# Arm.net
KiCad netlist of a schematic drawn in EAGLE
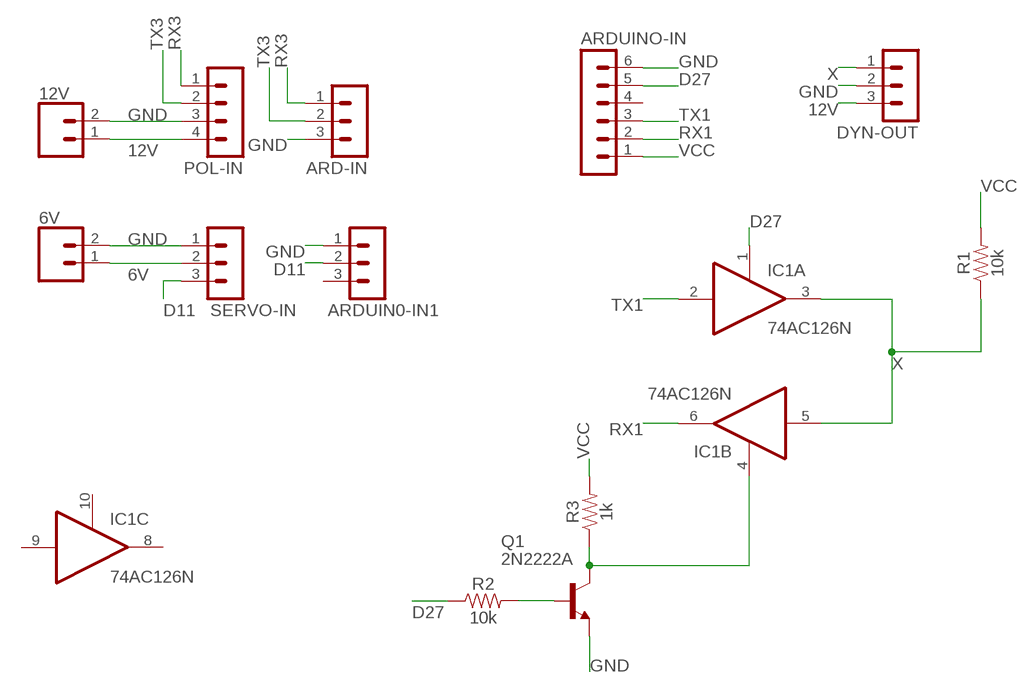
[diagram p0: schematic, sheet 1]

(export (version "E")
  (design (tool "Eeschema 10.0.6"))
  (components
    (comp (ref "6V")
      (value "CONN_021X02_NO_SILK")
      (footprint "eagle-import:1X02_NO_SILK")
      (libsource (lib "eagle-import") (part "CONN_021X02_NO_SILK"))
    )
    (comp (ref "12V")
      (value "CONN_021X02_NO_SILK")
      (footprint "eagle-import:1X02_NO_SILK")
      (libsource (lib "eagle-import") (part "CONN_021X02_NO_SILK"))
    )
    (comp (ref "ARD-IN")
      (value "MA03-1")
      (footprint "eagle-import:MA03-1")
      (libsource (lib "eagle-import") (part "MA03-1"))
    )
    (comp (ref "ARDUIN0-IN1")
      (value "MA03-1")
      (footprint "eagle-import:MA03-1")
      (libsource (lib "eagle-import") (part "MA03-1"))
    )
    (comp (ref "ARDUINO-IN")
      (value "MA06-1")
      (footprint "eagle-import:MA06-1")
      (libsource (lib "eagle-import") (part "MA06-1"))
    )
    (comp (ref "DYN-OUT")
      (value "MA03-1")
      (footprint "eagle-import:MA03-1")
      (libsource (lib "eagle-import") (part "MA03-1"))
    )
    (comp (ref "IC1")
      (value "74AC126N")
      (footprint "eagle-import:DIL14")
      (libsource (lib "eagle-import") (part "74126NAC"))
    )
    (comp (ref "POL-IN")
      (value "MA04-1")
      (footprint "eagle-import:MA04-1")
      (libsource (lib "eagle-import") (part "MA04-1"))
    )
    (comp (ref "Q1")
      (value "2N2222A")
      (footprint "eagle-import:TO18")
      (libsource (lib "eagle-import") (part "2N2222A"))
    )
    (comp (ref "R1")
      (value "10k")
      (footprint "eagle-import:AXIAL-0.3")
      (libsource (lib "eagle-import") (part "1KOHM-HORIZ-1/4W-1%"))
    )
    (comp (ref "R2")
      (value "10k")
      (footprint "eagle-import:AXIAL-0.3")
      (libsource (lib "eagle-import") (part "1KOHM-HORIZ-1/4W-1%"))
    )
    (comp (ref "R3")
      (value "1k")
      (footprint "eagle-import:AXIAL-0.3")
      (libsource (lib "eagle-import") (part "1KOHM-HORIZ-1/4W-1%"))
    )
    (comp (ref "SERVO-IN")
      (value "MA03-1")
      (footprint "eagle-import:MA03-1")
      (libsource (lib "eagle-import") (part "MA03-1"))
    )
  )
  (nets
    (net (code "1") (name "/6V") (class "Default")
      (node (ref "6V") (pin "1") (pinfunction "1_1") (pintype "passive"))
      (node (ref "SERVO-IN") (pin "2") (pinfunction "2_2") (pintype "passive"))
    )
    (net (code "2") (name "/12V") (class "Default")
      (node (ref "12V") (pin "1") (pinfunction "1_1") (pintype "passive"))
      (node (ref "DYN-OUT") (pin "3") (pinfunction "3_3") (pintype "passive"))
      (node (ref "POL-IN") (pin "4") (pinfunction "4_4") (pintype "passive"))
    )
    (net (code "3") (name "/D11") (class "Default")
      (node (ref "ARDUIN0-IN1") (pin "2") (pinfunction "2_2") (pintype "passive"))
      (node (ref "SERVO-IN") (pin "3") (pinfunction "3_3") (pintype "passive"))
    )
    (net (code "4") (name "/D27") (class "Default")
      (node (ref "ARDUINO-IN") (pin "5") (pinfunction "5_5") (pintype "passive"))
      (node (ref "IC1") (pin "1") (pinfunction "OE_1") (pintype "input"))
      (node (ref "R2") (pin "P$1") (pinfunction "1_P$1") (pintype "passive"))
    )
    (net (code "5") (name "/GND") (class "Default")
      (node (ref "12V") (pin "2") (pinfunction "2_2") (pintype "passive"))
      (node (ref "6V") (pin "2") (pinfunction "2_2") (pintype "passive"))
      (node (ref "ARD-IN") (pin "3") (pinfunction "3_3") (pintype "passive"))
      (node (ref "ARDUIN0-IN1") (pin "1") (pinfunction "1_1") (pintype "passive"))
      (node (ref "ARDUINO-IN") (pin "6") (pinfunction "6_6") (pintype "passive"))
      (node (ref "DYN-OUT") (pin "2") (pinfunction "2_2") (pintype "passive"))
      (node (ref "POL-IN") (pin "3") (pinfunction "3_3") (pintype "passive"))
      (node (ref "Q1") (pin "1") (pinfunction "E_1") (pintype "passive"))
      (node (ref "SERVO-IN") (pin "1") (pinfunction "1_1") (pintype "passive"))
    )
    (net (code "6") (name "/RX1") (class "Default")
      (node (ref "ARDUINO-IN") (pin "2") (pinfunction "2_2") (pintype "passive"))
      (node (ref "IC1") (pin "6") (pinfunction "O_6") (pintype "output"))
    )
    (net (code "7") (name "/RX3") (class "Default")
      (node (ref "ARD-IN") (pin "1") (pinfunction "1_1") (pintype "passive"))
      (node (ref "POL-IN") (pin "1") (pinfunction "1_1") (pintype "passive"))
    )
    (net (code "8") (name "/TX1") (class "Default")
      (node (ref "ARDUINO-IN") (pin "3") (pinfunction "3_3") (pintype "passive"))
      (node (ref "IC1") (pin "2") (pinfunction "I_2") (pintype "input"))
    )
    (net (code "9") (name "/TX3") (class "Default")
      (node (ref "ARD-IN") (pin "2") (pinfunction "2_2") (pintype "passive"))
      (node (ref "POL-IN") (pin "2") (pinfunction "2_2") (pintype "passive"))
    )
    (net (code "10") (name "/VCC") (class "Default")
      (node (ref "ARDUINO-IN") (pin "1") (pinfunction "1_1") (pintype "passive"))
      (node (ref "R1") (pin "P$2") (pinfunction "2_P$2") (pintype "passive"))
      (node (ref "R3") (pin "P$2") (pinfunction "2_P$2") (pintype "passive"))
    )
    (net (code "11") (name "/X") (class "Default")
      (node (ref "DYN-OUT") (pin "1") (pinfunction "1_1") (pintype "passive"))
      (node (ref "IC1") (pin "3") (pinfunction "O_3") (pintype "output"))
      (node (ref "IC1") (pin "5") (pinfunction "I_5") (pintype "input"))
      (node (ref "R1") (pin "P$1") (pinfunction "1_P$1") (pintype "passive"))
    )
    (net (code "12") (name "Net-(IC1B-OE)") (class "Default")
      (node (ref "IC1") (pin "4") (pinfunction "OE_4") (pintype "input"))
      (node (ref "Q1") (pin "3") (pinfunction "C_3") (pintype "passive"))
      (node (ref "R3") (pin "P$1") (pinfunction "1_P$1") (pintype "passive"))
    )
    (net (code "13") (name "Net-(Q1-B)") (class "Default")
      (node (ref "Q1") (pin "2") (pinfunction "B_2") (pintype "passive"))
      (node (ref "R2") (pin "P$2") (pinfunction "2_P$2") (pintype "passive"))
    )
    (net (code "14") (name "unconnected-(ARDUIN0-IN1-Pad3)") (class "Default")
      (node (ref "ARDUIN0-IN1") (pin "3") (pinfunction "3_3") (pintype "passive"))
    )
    (net (code "15") (name "unconnected-(ARDUINO-IN-Pad4)") (class "Default")
      (node (ref "ARDUINO-IN") (pin "4") (pinfunction "4_4") (pintype "passive"))
    )
    (net (code "16") (name "unconnected-(IC1C-I-Pad9)") (class "Default")
      (node (ref "IC1") (pin "9") (pinfunction "I_9") (pintype "input"))
    )
    (net (code "17") (name "unconnected-(IC1C-O-Pad8)") (class "Default")
      (node (ref "IC1") (pin "8") (pinfunction "O_8") (pintype "output"))
    )
    (net (code "18") (name "unconnected-(IC1C-OE-Pad10)") (class "Default")
      (node (ref "IC1") (pin "10") (pinfunction "OE_10") (pintype "input"))
    )
  )
)
